# PCG.net
KiCad netlist of a schematic drawn in EAGLE
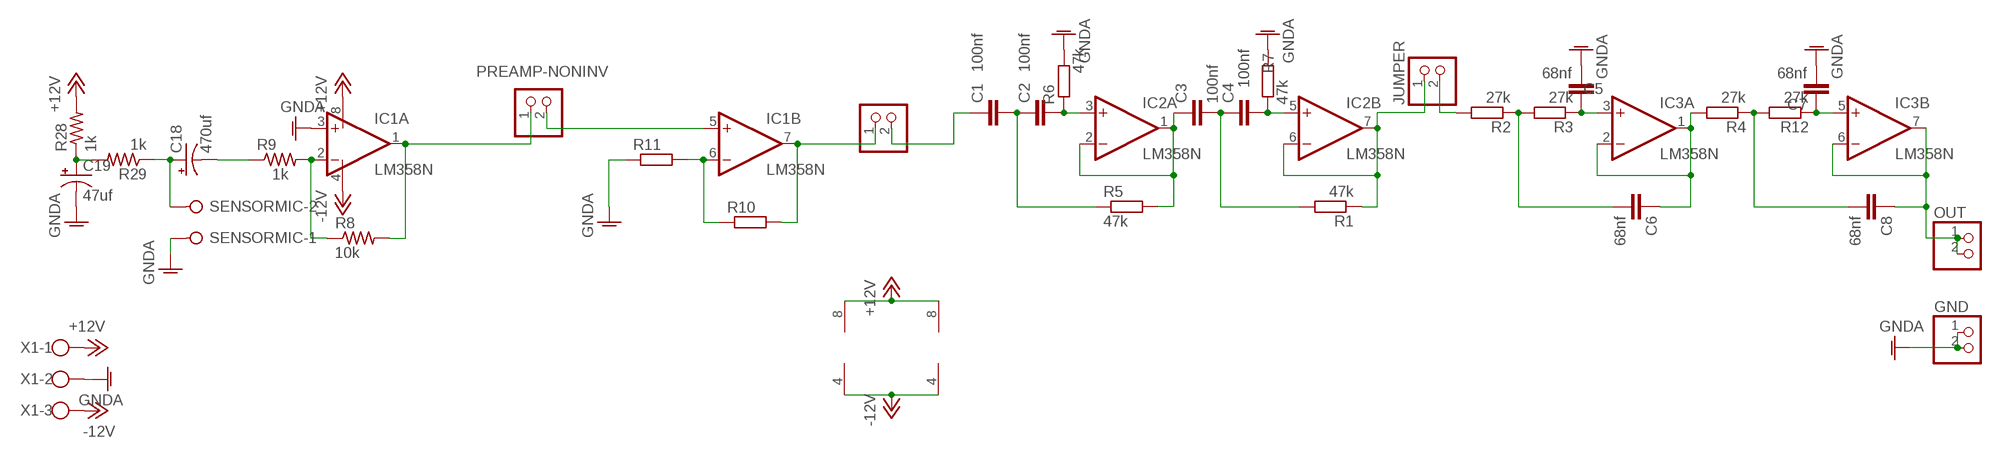
[diagram p0: schematic, sheet 1]

(export (version "E")
  (design (tool "Eeschema 10.0.6"))
  (components
    (comp (ref "C1")
      (value "100nf")
      (footprint "eagle-import:C050-025X075")
      (libsource (lib "eagle-import") (part "C-EU050-025X075"))
    )
    (comp (ref "C2")
      (value "100nf")
      (footprint "eagle-import:C050-025X075")
      (libsource (lib "eagle-import") (part "C-EU050-025X075"))
    )
    (comp (ref "C3")
      (value "100nf")
      (footprint "eagle-import:C050-025X075")
      (libsource (lib "eagle-import") (part "C-EU050-025X075"))
    )
    (comp (ref "C4")
      (value "100nf")
      (footprint "eagle-import:C050-025X075")
      (libsource (lib "eagle-import") (part "C-EU050-025X075"))
    )
    (comp (ref "C5")
      (value "68nf")
      (footprint "eagle-import:C050-025X075")
      (libsource (lib "eagle-import") (part "C-EU050-025X075"))
    )
    (comp (ref "C6")
      (value "68nf")
      (footprint "eagle-import:C050-025X075")
      (libsource (lib "eagle-import") (part "C-EU050-025X075"))
    )
    (comp (ref "C7")
      (value "68nf")
      (footprint "eagle-import:C050-025X075")
      (libsource (lib "eagle-import") (part "C-EU050-025X075"))
    )
    (comp (ref "C8")
      (value "68nf")
      (footprint "eagle-import:C050-025X075")
      (libsource (lib "eagle-import") (part "C-EU050-025X075"))
    )
    (comp (ref "C18")
      (value "470uf")
      (footprint "eagle-import:E2,5-7")
      (libsource (lib "eagle-import") (part "CPOL-USE2.5-7"))
    )
    (comp (ref "C19")
      (value "47uf")
      (footprint "eagle-import:E2-5")
      (libsource (lib "eagle-import") (part "CPOL-USE2-5"))
    )
    (comp (ref "GND")
      (value "PINHD-1X2")
      (footprint "eagle-import:1X02")
      (libsource (lib "eagle-import") (part "PINHD-1X2"))
    )
    (comp (ref "IC1")
      (value "LM358N")
      (footprint "eagle-import:DIL08")
      (libsource (lib "eagle-import") (part "LM358N"))
    )
    (comp (ref "IC2")
      (value "LM358N")
      (footprint "eagle-import:DIL08")
      (libsource (lib "eagle-import") (part "LM358N"))
    )
    (comp (ref "IC3")
      (value "LM358N")
      (footprint "eagle-import:DIL08")
      (libsource (lib "eagle-import") (part "LM358N"))
    )
    (comp (ref "JUMPER")
      (value "PINHD-1X2")
      (footprint "eagle-import:1X02")
      (libsource (lib "eagle-import") (part "PINHD-1X2"))
    )
    (comp (ref "NONINV-BPF")
      (value "PINHD-1X2")
      (footprint "eagle-import:1X02")
      (libsource (lib "eagle-import") (part "PINHD-1X2"))
    )
    (comp (ref "OUT")
      (value "PINHD-1X2")
      (footprint "eagle-import:1X02")
      (libsource (lib "eagle-import") (part "PINHD-1X2"))
    )
    (comp (ref "PREAMP-NONINV")
      (value "PINHD-1X2")
      (footprint "eagle-import:1X02")
      (libsource (lib "eagle-import") (part "PINHD-1X2"))
    )
    (comp (ref "R1")
      (value "47k")
      (footprint "eagle-import:0207_10")
      (libsource (lib "eagle-import") (part "R-EU_0207/10"))
    )
    (comp (ref "R2")
      (value "27k")
      (footprint "eagle-import:0207_10")
      (libsource (lib "eagle-import") (part "R-EU_0207/10"))
    )
    (comp (ref "R3")
      (value "27k")
      (footprint "eagle-import:0207_10")
      (libsource (lib "eagle-import") (part "R-EU_0207/10"))
    )
    (comp (ref "R4")
      (value "27k")
      (footprint "eagle-import:0207_10")
      (libsource (lib "eagle-import") (part "R-EU_0207/10"))
    )
    (comp (ref "R5")
      (value "47k")
      (footprint "eagle-import:0207_10")
      (libsource (lib "eagle-import") (part "R-EU_0207/10"))
    )
    (comp (ref "R6")
      (value "47k")
      (footprint "eagle-import:0207_10")
      (libsource (lib "eagle-import") (part "R-EU_0207/10"))
    )
    (comp (ref "R7")
      (value "47k")
      (footprint "eagle-import:0207_10")
      (libsource (lib "eagle-import") (part "R-EU_0207/10"))
    )
    (comp (ref "R8")
      (value "10k")
      (footprint "eagle-import:0207_7")
      (libsource (lib "eagle-import") (part "R-US_0207/7"))
    )
    (comp (ref "R9")
      (value "1k")
      (footprint "eagle-import:0207_7")
      (libsource (lib "eagle-import") (part "R-US_0207/7"))
    )
    (comp (ref "R10")
      (value "R-EU_0207/10")
      (footprint "eagle-import:0207_10")
      (libsource (lib "eagle-import") (part "R-EU_0207/10"))
    )
    (comp (ref "R11")
      (value "R-EU_0207/10")
      (footprint "eagle-import:0207_10")
      (libsource (lib "eagle-import") (part "R-EU_0207/10"))
    )
    (comp (ref "R12")
      (value "27k")
      (footprint "eagle-import:0207_10")
      (libsource (lib "eagle-import") (part "R-EU_0207/10"))
    )
    (comp (ref "R28")
      (value "1k")
      (footprint "eagle-import:0207_7")
      (libsource (lib "eagle-import") (part "R-US_0207/7"))
    )
    (comp (ref "R29")
      (value "1k")
      (footprint "eagle-import:0207_7")
      (libsource (lib "eagle-import") (part "R-US_0207/7"))
    )
    (comp (ref "SENSORMIC")
      (value "W237-02P")
      (footprint "eagle-import:W237-132")
      (libsource (lib "eagle-import") (part "W237-02P"))
    )
    (comp (ref "X1")
      (value "W237-103")
      (footprint "eagle-import:W237-103")
      (fields (field (name "MPN") "237-103"))
      (libsource (lib "eagle-import") (part "W237-103"))
    )
  )
  (nets
    (net (code "1") (name "+12V") (class "Default")
      (node (ref "IC1") (pin "8") (pinfunction "V+_8") (pintype "power_in"))
      (node (ref "IC2") (pin "8") (pinfunction "V+_8") (pintype "power_in"))
      (node (ref "IC3") (pin "8") (pinfunction "V+_8") (pintype "power_in"))
      (node (ref "R28") (pin "2") (pinfunction "2_2") (pintype "passive"))
      (node (ref "X1") (pin "1") (pinfunction "KL_1") (pintype "passive"))
    )
    (net (code "2") (name "-12V") (class "Default")
      (node (ref "IC1") (pin "4") (pinfunction "V-_4") (pintype "power_in"))
      (node (ref "IC2") (pin "4") (pinfunction "V-_4") (pintype "power_in"))
      (node (ref "IC3") (pin "4") (pinfunction "V-_4") (pintype "power_in"))
      (node (ref "X1") (pin "3") (pinfunction "KL_3") (pintype "passive"))
    )
    (net (code "3") (name "GNDA") (class "Default")
      (node (ref "C19") (pin "-") (pinfunction "-_-") (pintype "passive"))
      (node (ref "C5") (pin "2") (pinfunction "2_2") (pintype "passive"))
      (node (ref "C7") (pin "2") (pinfunction "2_2") (pintype "passive"))
      (node (ref "GND") (pin "1") (pinfunction "1_1") (pintype "passive"))
      (node (ref "GND") (pin "2") (pinfunction "2_2") (pintype "passive"))
      (node (ref "IC1") (pin "3") (pinfunction "+IN_3") (pintype "input"))
      (node (ref "R11") (pin "1") (pinfunction "1_1") (pintype "passive"))
      (node (ref "R6") (pin "2") (pinfunction "2_2") (pintype "passive"))
      (node (ref "R7") (pin "2") (pinfunction "2_2") (pintype "passive"))
      (node (ref "SENSORMIC") (pin "1") (pinfunction "KL_1") (pintype "passive"))
      (node (ref "X1") (pin "2") (pinfunction "KL_2") (pintype "passive"))
    )
    (net (code "4") (name "Net-(C1-Pad1)") (class "Default")
      (node (ref "C1") (pin "1") (pinfunction "1_1") (pintype "passive"))
      (node (ref "NONINV-BPF") (pin "2") (pinfunction "2_2") (pintype "passive"))
    )
    (net (code "5") (name "Net-(C1-Pad2)") (class "Default")
      (node (ref "C1") (pin "2") (pinfunction "2_2") (pintype "passive"))
      (node (ref "C2") (pin "1") (pinfunction "1_1") (pintype "passive"))
      (node (ref "R5") (pin "1") (pinfunction "1_1") (pintype "passive"))
    )
    (net (code "6") (name "Net-(C3-Pad2)") (class "Default")
      (node (ref "C3") (pin "2") (pinfunction "2_2") (pintype "passive"))
      (node (ref "C4") (pin "1") (pinfunction "1_1") (pintype "passive"))
      (node (ref "R1") (pin "2") (pinfunction "2_2") (pintype "passive"))
    )
    (net (code "7") (name "Net-(C6-Pad2)") (class "Default")
      (node (ref "C6") (pin "2") (pinfunction "2_2") (pintype "passive"))
      (node (ref "R2") (pin "1") (pinfunction "1_1") (pintype "passive"))
      (node (ref "R3") (pin "2") (pinfunction "2_2") (pintype "passive"))
    )
    (net (code "8") (name "Net-(C8-Pad2)") (class "Default")
      (node (ref "C8") (pin "2") (pinfunction "2_2") (pintype "passive"))
      (node (ref "R12") (pin "2") (pinfunction "2_2") (pintype "passive"))
      (node (ref "R4") (pin "1") (pinfunction "1_1") (pintype "passive"))
    )
    (net (code "9") (name "Net-(C18-Pad-)") (class "Default")
      (node (ref "C18") (pin "-") (pinfunction "-_-") (pintype "passive"))
      (node (ref "R9") (pin "1") (pinfunction "1_1") (pintype "passive"))
    )
    (net (code "10") (name "Net-(C19-Pad+)") (class "Default")
      (node (ref "C19") (pin "+") (pinfunction "+_+") (pintype "passive"))
      (node (ref "R28") (pin "1") (pinfunction "1_1") (pintype "passive"))
      (node (ref "R29") (pin "2") (pinfunction "2_2") (pintype "passive"))
    )
    (net (code "11") (name "Net-(IC1A--IN)") (class "Default")
      (node (ref "IC1") (pin "2") (pinfunction "-IN_2") (pintype "input"))
      (node (ref "R8") (pin "1") (pinfunction "1_1") (pintype "passive"))
      (node (ref "R9") (pin "2") (pinfunction "2_2") (pintype "passive"))
    )
    (net (code "12") (name "Net-(IC1A-OUT)") (class "Default")
      (node (ref "IC1") (pin "1") (pinfunction "OUT_1") (pintype "output"))
      (node (ref "PREAMP-NONINV") (pin "1") (pinfunction "1_1") (pintype "passive"))
      (node (ref "R8") (pin "2") (pinfunction "2_2") (pintype "passive"))
    )
    (net (code "13") (name "Net-(IC1B-+IN)") (class "Default")
      (node (ref "IC1") (pin "5") (pinfunction "+IN_5") (pintype "input"))
      (node (ref "PREAMP-NONINV") (pin "2") (pinfunction "2_2") (pintype "passive"))
    )
    (net (code "14") (name "Net-(IC1B--IN)") (class "Default")
      (node (ref "IC1") (pin "6") (pinfunction "-IN_6") (pintype "input"))
      (node (ref "R10") (pin "1") (pinfunction "1_1") (pintype "passive"))
      (node (ref "R11") (pin "2") (pinfunction "2_2") (pintype "passive"))
    )
    (net (code "15") (name "Net-(IC1B-OUT)") (class "Default")
      (node (ref "IC1") (pin "7") (pinfunction "OUT_7") (pintype "output"))
      (node (ref "NONINV-BPF") (pin "1") (pinfunction "1_1") (pintype "passive"))
      (node (ref "R10") (pin "2") (pinfunction "2_2") (pintype "passive"))
    )
    (net (code "16") (name "Net-(IC2A-+IN)") (class "Default")
      (node (ref "C2") (pin "2") (pinfunction "2_2") (pintype "passive"))
      (node (ref "IC2") (pin "3") (pinfunction "+IN_3") (pintype "input"))
      (node (ref "R6") (pin "1") (pinfunction "1_1") (pintype "passive"))
    )
    (net (code "17") (name "Net-(IC2A--IN)") (class "Default")
      (node (ref "C3") (pin "1") (pinfunction "1_1") (pintype "passive"))
      (node (ref "IC2") (pin "1") (pinfunction "OUT_1") (pintype "output"))
      (node (ref "IC2") (pin "2") (pinfunction "-IN_2") (pintype "input"))
      (node (ref "R5") (pin "2") (pinfunction "2_2") (pintype "passive"))
    )
    (net (code "18") (name "Net-(IC2B-+IN)") (class "Default")
      (node (ref "C4") (pin "2") (pinfunction "2_2") (pintype "passive"))
      (node (ref "IC2") (pin "5") (pinfunction "+IN_5") (pintype "input"))
      (node (ref "R7") (pin "1") (pinfunction "1_1") (pintype "passive"))
    )
    (net (code "19") (name "Net-(IC2B--IN)") (class "Default")
      (node (ref "IC2") (pin "6") (pinfunction "-IN_6") (pintype "input"))
      (node (ref "IC2") (pin "7") (pinfunction "OUT_7") (pintype "output"))
      (node (ref "JUMPER") (pin "1") (pinfunction "1_1") (pintype "passive"))
      (node (ref "R1") (pin "1") (pinfunction "1_1") (pintype "passive"))
    )
    (net (code "20") (name "Net-(IC3A-+IN)") (class "Default")
      (node (ref "C5") (pin "1") (pinfunction "1_1") (pintype "passive"))
      (node (ref "IC3") (pin "3") (pinfunction "+IN_3") (pintype "input"))
      (node (ref "R3") (pin "1") (pinfunction "1_1") (pintype "passive"))
    )
    (net (code "21") (name "Net-(IC3A--IN)") (class "Default")
      (node (ref "C6") (pin "1") (pinfunction "1_1") (pintype "passive"))
      (node (ref "IC3") (pin "1") (pinfunction "OUT_1") (pintype "output"))
      (node (ref "IC3") (pin "2") (pinfunction "-IN_2") (pintype "input"))
      (node (ref "R4") (pin "2") (pinfunction "2_2") (pintype "passive"))
    )
    (net (code "22") (name "Net-(IC3B-+IN)") (class "Default")
      (node (ref "C7") (pin "1") (pinfunction "1_1") (pintype "passive"))
      (node (ref "IC3") (pin "5") (pinfunction "+IN_5") (pintype "input"))
      (node (ref "R12") (pin "1") (pinfunction "1_1") (pintype "passive"))
    )
    (net (code "23") (name "Net-(IC3B--IN)") (class "Default")
      (node (ref "C8") (pin "1") (pinfunction "1_1") (pintype "passive"))
      (node (ref "IC3") (pin "6") (pinfunction "-IN_6") (pintype "input"))
      (node (ref "IC3") (pin "7") (pinfunction "OUT_7") (pintype "output"))
      (node (ref "OUT") (pin "1") (pinfunction "1_1") (pintype "passive"))
      (node (ref "OUT") (pin "2") (pinfunction "2_2") (pintype "passive"))
    )
    (net (code "24") (name "Net-(JUMPER-Pad2)") (class "Default")
      (node (ref "JUMPER") (pin "2") (pinfunction "2_2") (pintype "passive"))
      (node (ref "R2") (pin "2") (pinfunction "2_2") (pintype "passive"))
    )
    (net (code "25") (name "Net-(SENSORMICB-KL)") (class "Default")
      (node (ref "C18") (pin "+") (pinfunction "+_+") (pintype "passive"))
      (node (ref "R29") (pin "1") (pinfunction "1_1") (pintype "passive"))
      (node (ref "SENSORMIC") (pin "2") (pinfunction "KL_2") (pintype "passive"))
    )
  )
)
